# BrakeTemp.net
KiCad netlist of a schematic drawn in Altium Designer
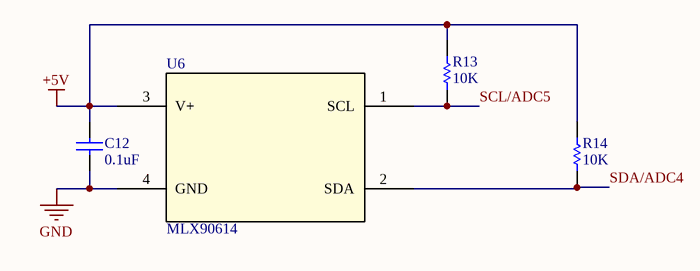
[diagram p0: BrakeTemp.SchDoc]

(export (version "E")
  (design (tool "Eeschema 10.0.6"))
  (components
    (comp (ref "C12")
      (value "0.1uF")
      (footprint "CAPC3216X170N")
      (description "Capacitor (Semiconductor SIM Model)")
      (fields
        (field (name "MANUFACTURER") "Murata")
        (field (name "MANUFACTURER PART NUMBER") "GRM31MR71H105KA88L")
        (field (name "PUBLISHER") "Altium Limited")
      )
      (libsource (lib "BrakeTempSensor") (part "Cap Semi_1"))
    )
    (comp (ref "R13")
      (value "10K")
      (footprint "RESC3216X60N")
      (description "Resistor")
      (fields
        (field (name "MANUFACTURER") "Stackpole Electronics")
        (field (name "MANUFACTURER PART NUMBER") "RNCP1206FTD10K0")
      )
      (libsource (lib "Miscellaneous Devices") (part "Res1"))
    )
    (comp (ref "R14")
      (value "10K")
      (footprint "RESC3216X60N")
      (description "Resistor")
      (fields
        (field (name "MANUFACTURER") "Stackpole Electronics")
        (field (name "MANUFACTURER PART NUMBER") "RNCP1206FTD10K0")
      )
      (libsource (lib "Miscellaneous Devices") (part "Res1"))
    )
    (comp (ref "U6")
      (value "MLX90614")
      (footprint "H_08_1")
      (description "Temp Sensor IR")
      (fields (field (name "MANUFACTURER_PART_NUMBER") "OP77FJZ"))
      (libsource (lib "BrakeTempSensor") (part "MLX90614"))
    )
  )
  (nets
    (net (code "1") (name "+5V") (class "Default")
      (node (ref "C12") (pin "2") (pinfunction "2_2") (pintype "passive"))
      (node (ref "R13") (pin "2") (pinfunction "2_2") (pintype "passive"))
      (node (ref "R14") (pin "2") (pinfunction "2_2") (pintype "passive"))
      (node (ref "U6") (pin "3") (pinfunction "V+_3") (pintype "passive"))
    )
    (net (code "2") (name "/SCL{slash}ADC5") (class "Default")
      (node (ref "R13") (pin "1") (pinfunction "1_1") (pintype "passive"))
      (node (ref "U6") (pin "1") (pinfunction "SCL_1") (pintype "passive"))
    )
    (net (code "3") (name "/SDA{slash}ADC4") (class "Default")
      (node (ref "R14") (pin "1") (pinfunction "1_1") (pintype "passive"))
      (node (ref "U6") (pin "2") (pinfunction "SDA_2") (pintype "passive"))
    )
    (net (code "4") (name "GND") (class "Default")
      (node (ref "C12") (pin "1") (pinfunction "1_1") (pintype "passive"))
      (node (ref "U6") (pin "4") (pinfunction "GND_4") (pintype "passive"))
    )
  )
)
